# PLC.net
KiCad netlist of a schematic drawn in Altium Designer
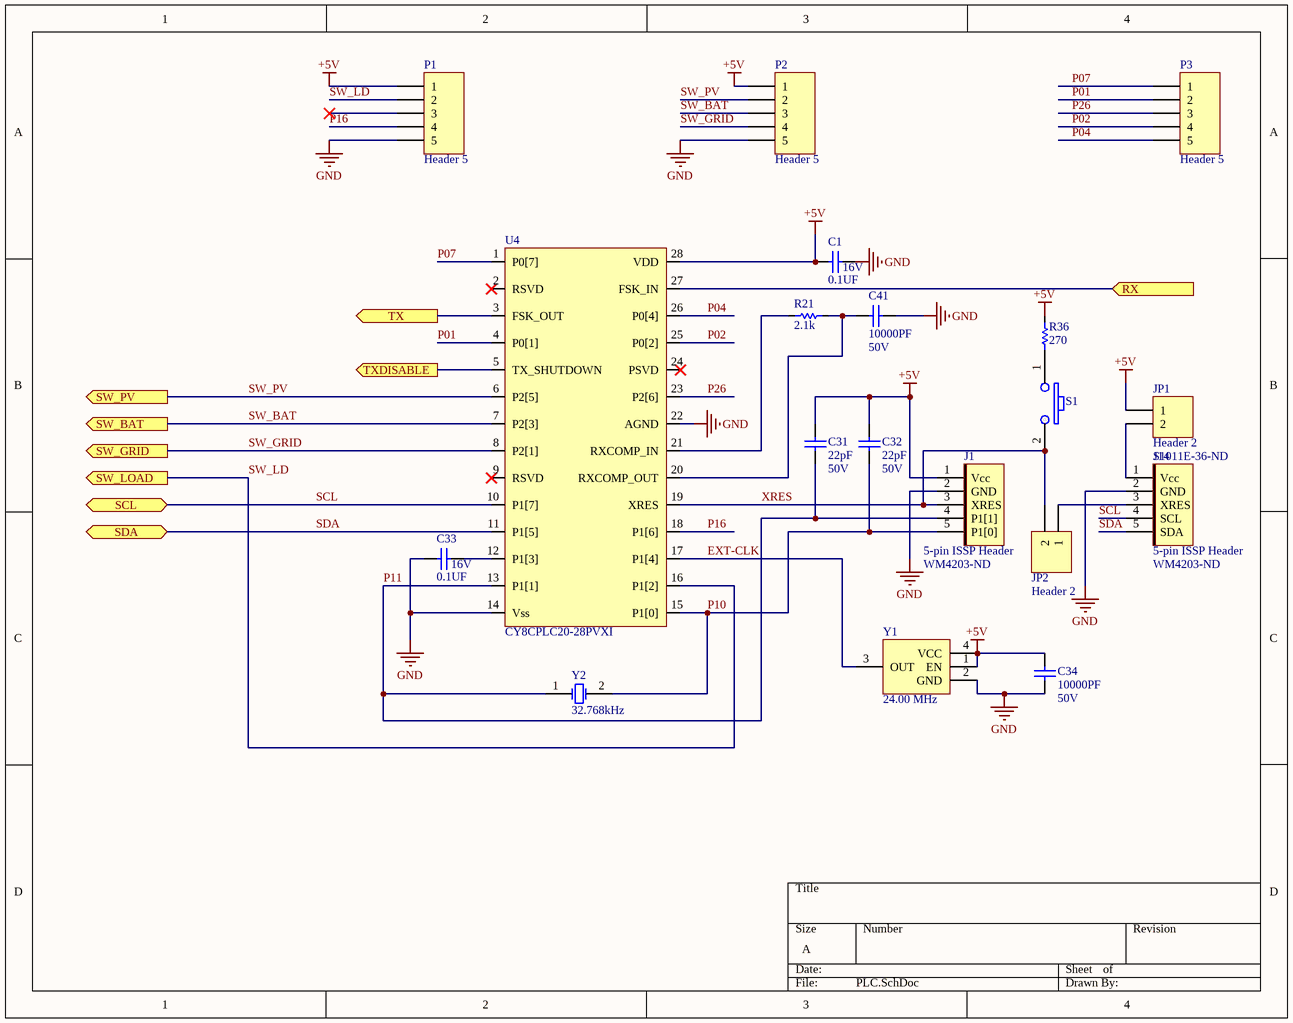
[diagram p0: PLC.SchDoc]

(export (version "E")
  (design (tool "Eeschema 10.0.6"))
  (components
    (comp (ref "C1")
      (value "GRM188R71C104KA01D")
      (footprint "CAPC1608X08N")
      (description "CAP CER 0.1UF 16V X7R 0603")
      (fields
        (field (name "MANUFACTURER") "Murata Electronics North America")
        (field (name "CAPACITANCE") "0.1UF")
        (field (name "VOLTAGE - RATED") "16V")
      )
      (libsource (lib "IntelligentJunctionBox") (part "GRM188R71C104KA01D"))
    )
    (comp (ref "C31")
      (value "GRM1885C1H220JA01D")
      (footprint "CAPC1608X08N")
      (description "CAP CER 22PF 50V C0G/NP0 0603")
      (fields
        (field (name "MANUFACTURER") "Murata Electronics North America")
        (field (name "CAPACITANCE") "22pF")
        (field (name "VOLTAGE - RATED") "50V")
      )
      (libsource (lib "IntelligentJunctionBox") (part "GRM1885C1H220JA01D"))
    )
    (comp (ref "C32")
      (value "GRM1885C1H220JA01D")
      (footprint "CAPC1608X08N")
      (description "CAP CER 22PF 50V C0G/NP0 0603")
      (fields
        (field (name "MANUFACTURER") "Murata Electronics North America")
        (field (name "CAPACITANCE") "22pF")
        (field (name "VOLTAGE - RATED") "50V")
      )
      (libsource (lib "IntelligentJunctionBox") (part "GRM1885C1H220JA01D"))
    )
    (comp (ref "C33")
      (value "GRM188R71C104KA01D")
      (footprint "CAPC1608X08N")
      (description "CAP CER 0.1UF 16V X7R 0603")
      (fields
        (field (name "MANUFACTURER") "Murata Electronics North America")
        (field (name "CAPACITANCE") "0.1UF")
        (field (name "VOLTAGE - RATED") "16V")
      )
      (libsource (lib "IntelligentJunctionBox") (part "GRM188R71C104KA01D"))
    )
    (comp (ref "C34")
      (value "GRM188R71H103KA01D")
      (footprint "CAPC1608X08N")
      (description "CAP CER 10000PF 50V X7R 0603")
      (fields
        (field (name "MANUFACTURER") "Murata Electronics North America")
        (field (name "CAPACITANCE") "10000PF")
        (field (name "VOLTAGE - RATED") "50V")
      )
      (libsource (lib "IntelligentJunctionBox") (part "GRM188R71H103KA01D"))
    )
    (comp (ref "C41")
      (value "GRM188R71H103KA01D")
      (footprint "CAPC1608X08N")
      (description "CAP CER 10000PF 50V X7R 0603")
      (fields
        (field (name "MANUFACTURER") "Murata Electronics North America")
        (field (name "CAPACITANCE") "10000PF")
        (field (name "VOLTAGE - RATED") "50V")
      )
      (libsource (lib "IntelligentJunctionBox") (part "GRM188R71H103KA01D"))
    )
    (comp (ref "J1")
      (value "5-pin ISSP Header")
      (footprint "ISPCON")
      (description "CONN HEADER 5POS .100 VERT TIN")
      (fields
        (field (name "MANUFACTURER") "Molex")
        (field (name "MANUFACTURER PART NUMBER") "22-23-2051")
        (field (name "SUPPLIER PART NUMBER 1") "WM4203-ND")
      )
      (libsource (lib "IntelligentJunctionBox") (part "ISSP_CON"))
    )
    (comp (ref "J14")
      (value "5-pin ISSP Header")
      (footprint "ISPCON")
      (description "CONN HEADER 5POS .100 VERT TIN")
      (fields
        (field (name "MANUFACTURER") "Molex")
        (field (name "MANUFACTURER PART NUMBER") "22-23-2051")
        (field (name "SUPPLIER PART NUMBER 1") "WM4203-ND")
      )
      (libsource (lib "IntelligentJunctionBox") (part "I2C_Connector"))
    )
    (comp (ref "JP1")
      (value "Header 2")
      (footprint "HDR1X2")
      (description "Header, 2-Pin")
      (fields
        (field (name "MANUFACTURER") "Sullins Connector Solutions")
        (field (name "MANUFACTURER PART NUMBER") "PBC36SAAN")
        (field (name "SUPPLIER PART NUMBER 1") "S1011E-36-ND")
      )
      (libsource (lib "IntelligentJunctionBox") (part "Header 2"))
    )
    (comp (ref "JP2")
      (value "Header 2")
      (footprint "HDR1X2")
      (description "Header, 2-Pin")
      (fields
        (field (name "MANUFACTURER") "Sullins Connector Solutions")
        (field (name "MANUFACTURER PART NUMBER") "PBC36SAAN")
      )
      (libsource (lib "") (part "Header 2_1"))
    )
    (comp (ref "P1")
      (value "Header 5")
      (footprint "HDR1X5")
      (description "Header, 5-Pin")
      (fields
        (field (name "MANUFACTURER PART NUMBER") "PBC36SAAN")
        (field (name "MANUFACTURER") "Sullins Connector Solutions")
      )
      (libsource (lib "IntelligentJunctionBox") (part "Header 5"))
    )
    (comp (ref "P2")
      (value "Header 5")
      (footprint "HDR1X5")
      (description "Header, 5-Pin")
      (fields
        (field (name "MANUFACTURER PART NUMBER") "PBC36SAAN")
        (field (name "MANUFACTURER") "Sullins Connector Solutions")
      )
      (libsource (lib "IntelligentJunctionBox") (part "Header 5"))
    )
    (comp (ref "P3")
      (value "Header 5")
      (footprint "HDR1X5")
      (description "Header, 5-Pin")
      (fields
        (field (name "MANUFACTURER PART NUMBER") "PBC36SAAN")
        (field (name "MANUFACTURER") "Sullins Connector Solutions")
      )
      (libsource (lib "IntelligentJunctionBox") (part "Header 5"))
    )
    (comp (ref "R21")
      (value "RC0603FR-072K1L")
      (footprint "RESC1608X06N")
      (description "RES SMD 2.1K OHM 1% 1/10W 0603")
      (fields (field (name "MANUFACTURER") "Yageo") (field (name "RESISTANCE") "2.1k"))
      (libsource (lib "IntelligentJunctionBox") (part "RC0603FR-072K1L"))
    )
    (comp (ref "R36")
      (value "RC0603JR-07270RL")
      (footprint "RESC1608X06N")
      (description "RES SMD 270 OHM 5% 1/10W 0603")
      (fields (field (name "MANUFACTURER") "Yageo") (field (name "RESISTANCE") "270"))
      (libsource (lib "IntelligentJunctionBox") (part "RC0603JR-07270RL"))
    )
    (comp (ref "S1")
      (value "B3F-1022")
      (footprint "STDSW")
      (description "Swtich, SPST")
      (fields (field (name "MANUFACTURER") "Omron"))
      (libsource (lib "IntelligentJunctionBox") (part "SPST"))
    )
    (comp (ref "U4")
      (value "CY8CPLC20-28PVXI")
      (footprint "SOP65P780X200-28N")
      (description "IC PLC PSOC CMOS 28SSOP")
      (fields (field (name "MANUFACTURER") "Cypress Semiconductor Corp"))
      (libsource (lib "IntelligentJunctionBox") (part "CY8CPLC20-28PVXI"))
    )
    (comp (ref "Y1")
      (value "24.00 MHz")
      (footprint "CSX-750F")
      (description "OSC XO 24.000MHZ CMOS TTL SMD")
      (fields
        (field (name "MANUFACTURER") "Citizen Finedevice Co Ltd")
        (field (name "MANUFACTURER PART NUMBER") "CSX-750FCC24000000T")
      )
      (libsource (lib "IntelligentJunctionBox") (part "CSX-750FCC24000000T"))
    )
    (comp (ref "Y2")
      (value "32.768kHz")
      (footprint "XTAL32K")
      (description "Crystal 32.768kHz 12.5pF")
      (fields (field (name "MANUFACTURER") "ECS Inc.") (field (name "MANUFACTURER PART NUMBER") "ECS-3X8X"))
      (libsource (lib "IntelligentJunctionBox") (part "XTAL"))
    )
  )
  (nets
    (net (code "1") (name "+5V") (class "Default")
      (node (ref "C1") (pin "1") (pinfunction "1_1") (pintype "passive"))
      (node (ref "C31") (pin "2") (pinfunction "2_2") (pintype "passive"))
      (node (ref "C32") (pin "2") (pinfunction "2_2") (pintype "passive"))
      (node (ref "C34") (pin "2") (pinfunction "2_2") (pintype "passive"))
      (node (ref "J1") (pin "1") (pinfunction "Vcc_1") (pintype "passive"))
      (node (ref "JP1") (pin "1") (pinfunction "1_1") (pintype "passive"))
      (node (ref "P1") (pin "1") (pinfunction "1_1") (pintype "passive"))
      (node (ref "P2") (pin "1") (pinfunction "1_1") (pintype "passive"))
      (node (ref "R36") (pin "2") (pinfunction "2_2") (pintype "passive"))
      (node (ref "U4") (pin "28") (pinfunction "VDD_28") (pintype "passive"))
      (node (ref "Y1") (pin "1") (pinfunction "EN_1") (pintype "passive"))
      (node (ref "Y1") (pin "4") (pinfunction "VCC_4") (pintype "passive"))
    )
    (net (code "2") (name "/EXT-CLK") (class "Default")
      (node (ref "U4") (pin "17") (pinfunction "P1[4]_17") (pintype "passive"))
      (node (ref "Y1") (pin "3") (pinfunction "OUT_3") (pintype "passive"))
    )
    (net (code "3") (name "/P01") (class "Default")
      (node (ref "P3") (pin "2") (pinfunction "2_2") (pintype "passive"))
      (node (ref "U4") (pin "4") (pinfunction "P0[1]_4") (pintype "passive"))
    )
    (net (code "4") (name "/P02") (class "Default")
      (node (ref "P3") (pin "4") (pinfunction "4_4") (pintype "passive"))
      (node (ref "U4") (pin "25") (pinfunction "P0[2]_25") (pintype "passive"))
    )
    (net (code "5") (name "/P04") (class "Default")
      (node (ref "P3") (pin "5") (pinfunction "5_5") (pintype "passive"))
      (node (ref "U4") (pin "26") (pinfunction "P0[4]_26") (pintype "passive"))
    )
    (net (code "6") (name "/P07") (class "Default")
      (node (ref "P3") (pin "1") (pinfunction "1_1") (pintype "passive"))
      (node (ref "U4") (pin "1") (pinfunction "P0[7]_1") (pintype "passive"))
    )
    (net (code "7") (name "/P10") (class "Default")
      (node (ref "C32") (pin "1") (pinfunction "1_1") (pintype "passive"))
      (node (ref "J1") (pin "5") (pinfunction "P1[0]_5") (pintype "passive"))
      (node (ref "U4") (pin "15") (pinfunction "P1[0]_15") (pintype "passive"))
      (node (ref "Y2") (pin "2") (pinfunction "OSC2_2") (pintype "passive"))
    )
    (net (code "8") (name "/P11") (class "Default")
      (node (ref "C31") (pin "1") (pinfunction "1_1") (pintype "passive"))
      (node (ref "J1") (pin "4") (pinfunction "P1[1]_4") (pintype "passive"))
      (node (ref "U4") (pin "13") (pinfunction "P1[1]_13") (pintype "passive"))
      (node (ref "Y2") (pin "1") (pinfunction "OSC1_1") (pintype "passive"))
    )
    (net (code "9") (name "/P16") (class "Default")
      (node (ref "P1") (pin "4") (pinfunction "4_4") (pintype "passive"))
      (node (ref "U4") (pin "18") (pinfunction "P1[6]_18") (pintype "passive"))
    )
    (net (code "10") (name "/P26") (class "Default")
      (node (ref "P3") (pin "3") (pinfunction "3_3") (pintype "passive"))
      (node (ref "U4") (pin "23") (pinfunction "P2[6]_23") (pintype "passive"))
    )
    (net (code "11") (name "/RX") (class "Default")
      (node (ref "U4") (pin "27") (pinfunction "FSK_IN_27") (pintype "passive"))
    )
    (net (code "12") (name "/SCL") (class "Default")
      (node (ref "J14") (pin "4") (pinfunction "SCL_4") (pintype "passive"))
      (node (ref "U4") (pin "10") (pinfunction "P1[7]_10") (pintype "passive"))
    )
    (net (code "13") (name "/SDA") (class "Default")
      (node (ref "J14") (pin "5") (pinfunction "SDA_5") (pintype "passive"))
      (node (ref "U4") (pin "11") (pinfunction "P1[5]_11") (pintype "passive"))
    )
    (net (code "14") (name "/SW_BAT") (class "Default")
      (node (ref "P2") (pin "3") (pinfunction "3_3") (pintype "passive"))
      (node (ref "U4") (pin "7") (pinfunction "P2[3]_7") (pintype "passive"))
    )
    (net (code "15") (name "/SW_GRID") (class "Default")
      (node (ref "P2") (pin "4") (pinfunction "4_4") (pintype "passive"))
      (node (ref "U4") (pin "8") (pinfunction "P2[1]_8") (pintype "passive"))
    )
    (net (code "16") (name "/SW_LD") (class "Default")
      (node (ref "P1") (pin "2") (pinfunction "2_2") (pintype "passive"))
      (node (ref "U4") (pin "16") (pinfunction "P1[2]_16") (pintype "passive"))
    )
    (net (code "17") (name "/SW_PV") (class "Default")
      (node (ref "P2") (pin "2") (pinfunction "2_2") (pintype "passive"))
      (node (ref "U4") (pin "6") (pinfunction "P2[5]_6") (pintype "passive"))
    )
    (net (code "18") (name "/TX") (class "Default")
      (node (ref "U4") (pin "3") (pinfunction "FSK_OUT_3") (pintype "passive"))
    )
    (net (code "19") (name "/TXDISABLE") (class "Default")
      (node (ref "U4") (pin "5") (pinfunction "TX_SHUTDOWN_5") (pintype "passive"))
    )
    (net (code "20") (name "/XRES") (class "Default")
      (node (ref "J1") (pin "3") (pinfunction "XRES_3") (pintype "passive"))
      (node (ref "JP2") (pin "2") (pinfunction "2_2") (pintype "passive"))
      (node (ref "S1") (pin "2") (pinfunction "NO_2") (pintype "passive"))
      (node (ref "U4") (pin "19") (pinfunction "XRES_19") (pintype "passive"))
    )
    (net (code "21") (name "GND") (class "Default")
      (node (ref "C1") (pin "2") (pinfunction "2_2") (pintype "passive"))
      (node (ref "C33") (pin "1") (pinfunction "1_1") (pintype "passive"))
      (node (ref "C34") (pin "1") (pinfunction "1_1") (pintype "passive"))
      (node (ref "C41") (pin "1") (pinfunction "1_1") (pintype "passive"))
      (node (ref "J1") (pin "2") (pinfunction "GND_2") (pintype "passive"))
      (node (ref "J14") (pin "2") (pinfunction "GND_2") (pintype "passive"))
      (node (ref "P1") (pin "5") (pinfunction "5_5") (pintype "passive"))
      (node (ref "P2") (pin "5") (pinfunction "5_5") (pintype "passive"))
      (node (ref "U4") (pin "14") (pinfunction "Vss_14") (pintype "passive"))
      (node (ref "U4") (pin "22") (pinfunction "AGND_22") (pintype "passive"))
      (node (ref "Y1") (pin "2") (pinfunction "GND_2") (pintype "passive"))
    )
    (net (code "22") (name "Net-(J14-Vcc)") (class "Default")
      (node (ref "J14") (pin "1") (pinfunction "Vcc_1") (pintype "passive"))
      (node (ref "JP1") (pin "2") (pinfunction "2_2") (pintype "passive"))
    )
    (net (code "23") (name "Net-(J14-XRES)") (class "Default")
      (node (ref "J14") (pin "3") (pinfunction "XRES_3") (pintype "passive"))
      (node (ref "JP2") (pin "1") (pinfunction "1_1") (pintype "passive"))
    )
    (net (code "24") (name "Net-(S1-C)") (class "Default")
      (node (ref "R36") (pin "1") (pinfunction "1_1") (pintype "passive"))
      (node (ref "S1") (pin "1") (pinfunction "C_1") (pintype "passive"))
    )
    (net (code "25") (name "Net-(U4-P1[3])") (class "Default")
      (node (ref "C33") (pin "2") (pinfunction "2_2") (pintype "passive"))
      (node (ref "U4") (pin "12") (pinfunction "P1[3]_12") (pintype "passive"))
    )
    (net (code "26") (name "Net-(U4-RXCOMP_IN)") (class "Default")
      (node (ref "R21") (pin "1") (pinfunction "1_1") (pintype "passive"))
      (node (ref "U4") (pin "21") (pinfunction "RXCOMP_IN_21") (pintype "passive"))
    )
    (net (code "27") (name "Net-(U4-RXCOMP_OUT)") (class "Default")
      (node (ref "C41") (pin "2") (pinfunction "2_2") (pintype "passive"))
      (node (ref "R21") (pin "2") (pinfunction "2_2") (pintype "passive"))
      (node (ref "U4") (pin "20") (pinfunction "RXCOMP_OUT_20") (pintype "passive"))
    )
    (net (code "28") (name "unconnected-(P1-Pad3)") (class "Default")
      (node (ref "P1") (pin "3") (pinfunction "3_3") (pintype "passive+no_connect"))
    )
    (net (code "29") (name "unconnected-(U4-PSVD-Pad24)") (class "Default")
      (node (ref "U4") (pin "24") (pinfunction "PSVD_24") (pintype "passive+no_connect"))
    )
    (net (code "30") (name "unconnected-(U4-RSVD-Pad2)") (class "Default")
      (node (ref "U4") (pin "2") (pinfunction "RSVD_2") (pintype "passive+no_connect"))
    )
    (net (code "31") (name "unconnected-(U4-RSVD-Pad9)") (class "Default")
      (node (ref "U4") (pin "9") (pinfunction "RSVD_9") (pintype "passive+no_connect"))
    )
  )
)
